# Connectors.net
KiCad netlist of a schematic drawn in Altium Designer
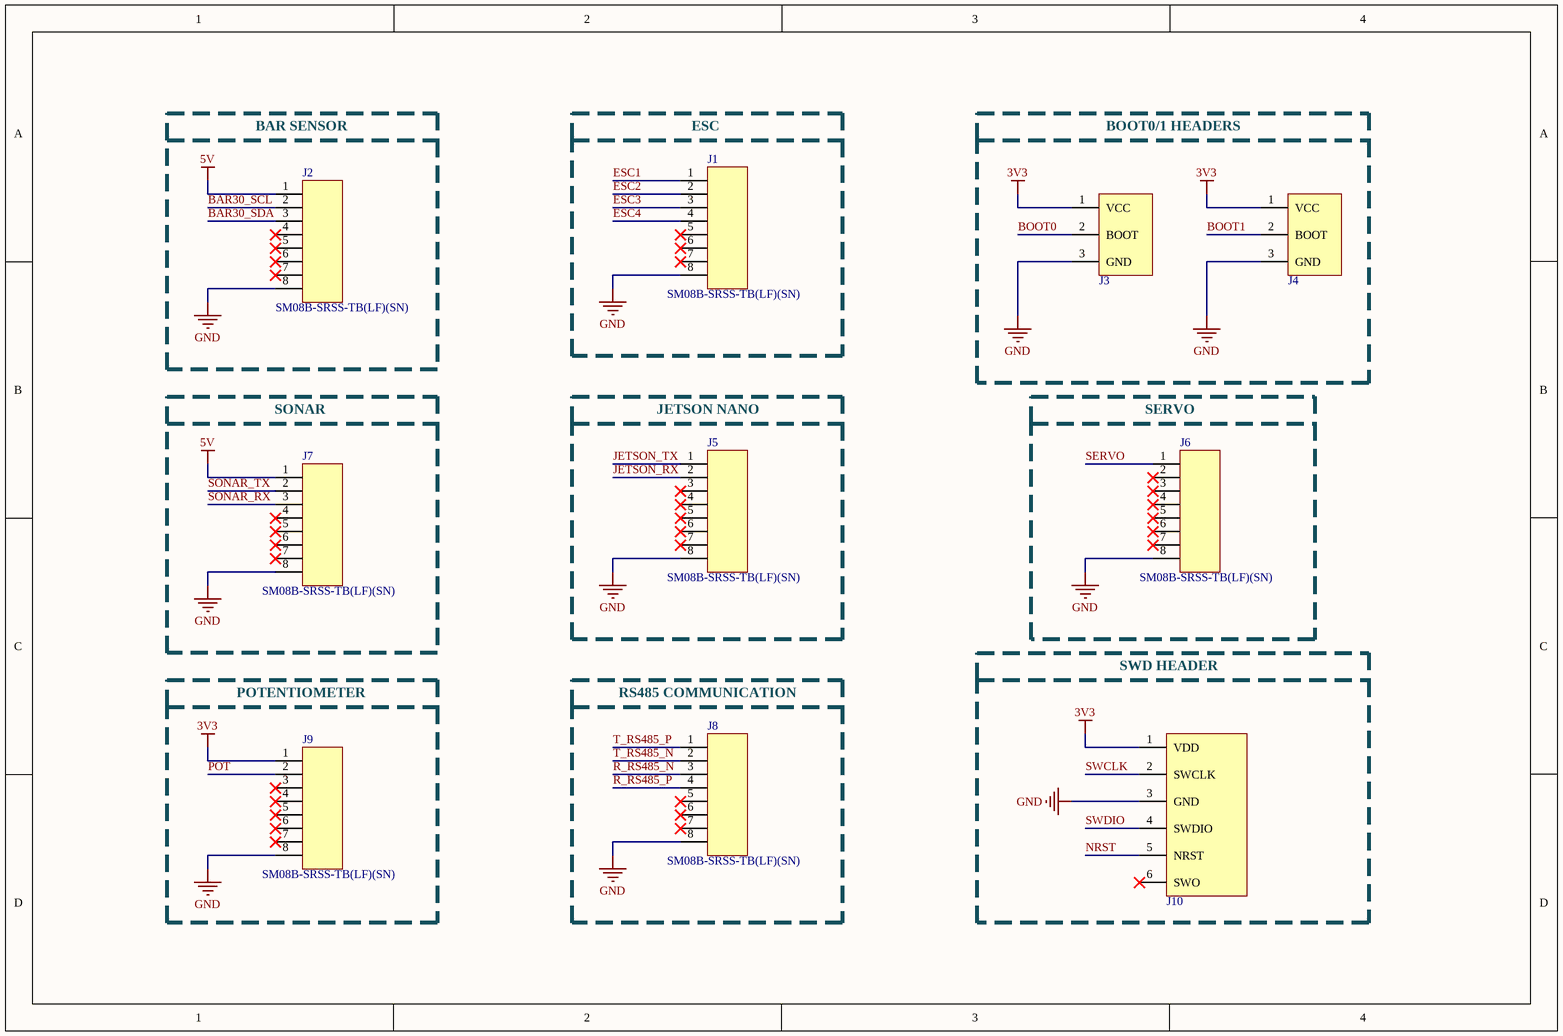
[diagram p0: Connectors.SchDoc]

(export (version "E")
  (design (tool "Eeschema 10.0.6"))
  (components
    (comp (ref "J1")
      (value "SM08B-SRSS-TB(LF)(SN)")
      (footprint "8 PIN HEADER")
      (description "Connector Header, Side Entry, SR Series, 8 Position, 1.00mm, 50V, Surface Mount, Tin, Natural")
      (fields (field (name "MANUFACTURER") "JST") (field (name "DESIGNED BY") "ADAK"))
      (libsource (lib "Integrated_Library5") (part "SM08B-SRSS-TB(LF)(SN)"))
    )
    (comp (ref "J2")
      (value "SM08B-SRSS-TB(LF)(SN)")
      (footprint "8 PIN HEADER")
      (description "Connector Header, Side Entry, SR Series, 8 Position, 1.00mm, 50V, Surface Mount, Tin, Natural")
      (fields (field (name "MANUFACTURER") "JST") (field (name "DESIGNED BY") "ADAK"))
      (libsource (lib "Integrated_Library5") (part "SM08B-SRSS-TB(LF)(SN)"))
    )
    (comp (ref "J3")
      (value "61300311121")
      (footprint "BOOT HEADER")
      (description "CONN HEADER VERT 3POS 2.54MM")
      (fields (field (name "MANUFACTURER") "Wurth Electronics") (field (name "DESIGNED BY") "ADAK"))
      (libsource (lib "Integrated_Library5") (part "61300311121"))
    )
    (comp (ref "J4")
      (value "61300311121")
      (footprint "BOOT HEADER")
      (description "CONN HEADER VERT 3POS 2.54MM")
      (fields (field (name "MANUFACTURER") "Wurth Electronics") (field (name "DESIGNED BY") "ADAK"))
      (libsource (lib "Integrated_Library5") (part "61300311121"))
    )
    (comp (ref "J5")
      (value "SM08B-SRSS-TB(LF)(SN)")
      (footprint "8 PIN HEADER")
      (description "Connector Header, Side Entry, SR Series, 8 Position, 1.00mm, 50V, Surface Mount, Tin, Natural")
      (fields (field (name "MANUFACTURER") "JST") (field (name "DESIGNED BY") "ADAK"))
      (libsource (lib "Integrated_Library5") (part "SM08B-SRSS-TB(LF)(SN)"))
    )
    (comp (ref "J6")
      (value "SM08B-SRSS-TB(LF)(SN)")
      (footprint "8 PIN HEADER")
      (description "Connector Header, Side Entry, SR Series, 8 Position, 1.00mm, 50V, Surface Mount, Tin, Natural")
      (fields (field (name "MANUFACTURER") "JST") (field (name "DESIGNED BY") "ADAK"))
      (libsource (lib "Integrated_Library5") (part "SM08B-SRSS-TB(LF)(SN)"))
    )
    (comp (ref "J7")
      (value "SM08B-SRSS-TB(LF)(SN)")
      (footprint "8 PIN HEADER")
      (description "Connector Header, Side Entry, SR Series, 8 Position, 1.00mm, 50V, Surface Mount, Tin, Natural")
      (fields (field (name "MANUFACTURER") "JST") (field (name "DESIGNED BY") "ADAK"))
      (libsource (lib "Integrated_Library5") (part "SM08B-SRSS-TB(LF)(SN)"))
    )
    (comp (ref "J8")
      (value "SM08B-SRSS-TB(LF)(SN)")
      (footprint "8 PIN HEADER")
      (description "Connector Header, Side Entry, SR Series, 8 Position, 1.00mm, 50V, Surface Mount, Tin, Natural")
      (fields (field (name "MANUFACTURER") "JST") (field (name "DESIGNED BY") "ADAK"))
      (libsource (lib "Integrated_Library5") (part "SM08B-SRSS-TB(LF)(SN)"))
    )
    (comp (ref "J9")
      (value "SM08B-SRSS-TB(LF)(SN)")
      (footprint "8 PIN HEADER")
      (description "Connector Header, Side Entry, SR Series, 8 Position, 1.00mm, 50V, Surface Mount, Tin, Natural")
      (fields (field (name "MANUFACTURER") "JST") (field (name "DESIGNED BY") "ADAK"))
      (libsource (lib "Integrated_Library5") (part "SM08B-SRSS-TB(LF)(SN)"))
    )
    (comp (ref "J10")
      (value "61300611121")
      (footprint "SWD HEADER")
      (description "CONN HEADER VERT 6POS 2.54MM")
      (fields (field (name "MANUFACTURER") "Wurth Electronics") (field (name "DESIGNED BY") "ADAK"))
      (libsource (lib "Integrated_Library5") (part "61300611121"))
    )
  )
  (nets
    (net (code "1") (name "/BAR30_SCL") (class "Default")
      (node (ref "J2") (pin "2") (pinfunction "2_2") (pintype "passive"))
    )
    (net (code "2") (name "/BAR30_SDA") (class "Default")
      (node (ref "J2") (pin "3") (pinfunction "3_3") (pintype "passive"))
    )
    (net (code "3") (name "/BOOT0") (class "Default")
      (node (ref "J3") (pin "2") (pinfunction "BOOT_2") (pintype "passive"))
    )
    (net (code "4") (name "/BOOT1") (class "Default")
      (node (ref "J4") (pin "2") (pinfunction "BOOT_2") (pintype "passive"))
    )
    (net (code "5") (name "/ESC1") (class "Default")
      (node (ref "J1") (pin "1") (pinfunction "1_1") (pintype "passive"))
    )
    (net (code "6") (name "/ESC2") (class "Default")
      (node (ref "J1") (pin "2") (pinfunction "2_2") (pintype "passive"))
    )
    (net (code "7") (name "/ESC3") (class "Default")
      (node (ref "J1") (pin "3") (pinfunction "3_3") (pintype "passive"))
    )
    (net (code "8") (name "/ESC4") (class "Default")
      (node (ref "J1") (pin "4") (pinfunction "4_4") (pintype "passive"))
    )
    (net (code "9") (name "/JETSON_RX") (class "Default")
      (node (ref "J5") (pin "2") (pinfunction "2_2") (pintype "passive"))
    )
    (net (code "10") (name "/JETSON_TX") (class "Default")
      (node (ref "J5") (pin "1") (pinfunction "1_1") (pintype "passive"))
    )
    (net (code "11") (name "/NRST") (class "Default")
      (node (ref "J10") (pin "5") (pinfunction "NRST_5") (pintype "passive"))
    )
    (net (code "12") (name "/POT") (class "Default")
      (node (ref "J9") (pin "2") (pinfunction "2_2") (pintype "passive"))
    )
    (net (code "13") (name "/R_RS485_N") (class "Default")
      (node (ref "J8") (pin "3") (pinfunction "3_3") (pintype "passive"))
    )
    (net (code "14") (name "/R_RS485_P") (class "Default")
      (node (ref "J8") (pin "4") (pinfunction "4_4") (pintype "passive"))
    )
    (net (code "15") (name "/SERVO") (class "Default")
      (node (ref "J6") (pin "1") (pinfunction "1_1") (pintype "passive"))
    )
    (net (code "16") (name "/SONAR_RX") (class "Default")
      (node (ref "J7") (pin "3") (pinfunction "3_3") (pintype "passive"))
    )
    (net (code "17") (name "/SONAR_TX") (class "Default")
      (node (ref "J7") (pin "2") (pinfunction "2_2") (pintype "passive"))
    )
    (net (code "18") (name "/SWCLK") (class "Default")
      (node (ref "J10") (pin "2") (pinfunction "SWCLK_2") (pintype "passive"))
    )
    (net (code "19") (name "/SWDIO") (class "Default")
      (node (ref "J10") (pin "4") (pinfunction "SWDIO_4") (pintype "passive"))
    )
    (net (code "20") (name "/T_RS485_N") (class "Default")
      (node (ref "J8") (pin "2") (pinfunction "2_2") (pintype "passive"))
    )
    (net (code "21") (name "/T_RS485_P") (class "Default")
      (node (ref "J8") (pin "1") (pinfunction "1_1") (pintype "passive"))
    )
    (net (code "22") (name "3V3") (class "Default")
      (node (ref "J10") (pin "1") (pinfunction "VDD_1") (pintype "passive"))
      (node (ref "J3") (pin "1") (pinfunction "VCC_1") (pintype "passive"))
      (node (ref "J4") (pin "1") (pinfunction "VCC_1") (pintype "passive"))
      (node (ref "J9") (pin "1") (pinfunction "1_1") (pintype "passive"))
    )
    (net (code "23") (name "5V") (class "Default")
      (node (ref "J2") (pin "1") (pinfunction "1_1") (pintype "passive"))
      (node (ref "J7") (pin "1") (pinfunction "1_1") (pintype "passive"))
    )
    (net (code "24") (name "GND") (class "Default")
      (node (ref "J1") (pin "8") (pinfunction "8_8") (pintype "passive"))
      (node (ref "J10") (pin "3") (pinfunction "GND_3") (pintype "passive"))
      (node (ref "J2") (pin "8") (pinfunction "8_8") (pintype "passive"))
      (node (ref "J3") (pin "3") (pinfunction "GND_3") (pintype "passive"))
      (node (ref "J4") (pin "3") (pinfunction "GND_3") (pintype "passive"))
      (node (ref "J5") (pin "8") (pinfunction "8_8") (pintype "passive"))
      (node (ref "J6") (pin "8") (pinfunction "8_8") (pintype "passive"))
      (node (ref "J7") (pin "8") (pinfunction "8_8") (pintype "passive"))
      (node (ref "J8") (pin "8") (pinfunction "8_8") (pintype "passive"))
      (node (ref "J9") (pin "8") (pinfunction "8_8") (pintype "passive"))
    )
    (net (code "25") (name "unconnected-(J1-Pad5)") (class "Default")
      (node (ref "J1") (pin "5") (pinfunction "5_5") (pintype "passive+no_connect"))
    )
    (net (code "26") (name "unconnected-(J1-Pad6)") (class "Default")
      (node (ref "J1") (pin "6") (pinfunction "6_6") (pintype "passive+no_connect"))
    )
    (net (code "27") (name "unconnected-(J1-Pad7)") (class "Default")
      (node (ref "J1") (pin "7") (pinfunction "7_7") (pintype "passive+no_connect"))
    )
    (net (code "28") (name "unconnected-(J2-Pad4)") (class "Default")
      (node (ref "J2") (pin "4") (pinfunction "4_4") (pintype "passive+no_connect"))
    )
    (net (code "29") (name "unconnected-(J2-Pad5)") (class "Default")
      (node (ref "J2") (pin "5") (pinfunction "5_5") (pintype "passive+no_connect"))
    )
    (net (code "30") (name "unconnected-(J2-Pad6)") (class "Default")
      (node (ref "J2") (pin "6") (pinfunction "6_6") (pintype "passive+no_connect"))
    )
    (net (code "31") (name "unconnected-(J2-Pad7)") (class "Default")
      (node (ref "J2") (pin "7") (pinfunction "7_7") (pintype "passive+no_connect"))
    )
    (net (code "32") (name "unconnected-(J5-Pad3)") (class "Default")
      (node (ref "J5") (pin "3") (pinfunction "3_3") (pintype "passive+no_connect"))
    )
    (net (code "33") (name "unconnected-(J5-Pad4)") (class "Default")
      (node (ref "J5") (pin "4") (pinfunction "4_4") (pintype "passive+no_connect"))
    )
    (net (code "34") (name "unconnected-(J5-Pad5)") (class "Default")
      (node (ref "J5") (pin "5") (pinfunction "5_5") (pintype "passive+no_connect"))
    )
    (net (code "35") (name "unconnected-(J5-Pad6)") (class "Default")
      (node (ref "J5") (pin "6") (pinfunction "6_6") (pintype "passive+no_connect"))
    )
    (net (code "36") (name "unconnected-(J5-Pad7)") (class "Default")
      (node (ref "J5") (pin "7") (pinfunction "7_7") (pintype "passive+no_connect"))
    )
    (net (code "37") (name "unconnected-(J6-Pad2)") (class "Default")
      (node (ref "J6") (pin "2") (pinfunction "2_2") (pintype "passive+no_connect"))
    )
    (net (code "38") (name "unconnected-(J6-Pad3)") (class "Default")
      (node (ref "J6") (pin "3") (pinfunction "3_3") (pintype "passive+no_connect"))
    )
    (net (code "39") (name "unconnected-(J6-Pad4)") (class "Default")
      (node (ref "J6") (pin "4") (pinfunction "4_4") (pintype "passive+no_connect"))
    )
    (net (code "40") (name "unconnected-(J6-Pad5)") (class "Default")
      (node (ref "J6") (pin "5") (pinfunction "5_5") (pintype "passive+no_connect"))
    )
    (net (code "41") (name "unconnected-(J6-Pad6)") (class "Default")
      (node (ref "J6") (pin "6") (pinfunction "6_6") (pintype "passive+no_connect"))
    )
    (net (code "42") (name "unconnected-(J6-Pad7)") (class "Default")
      (node (ref "J6") (pin "7") (pinfunction "7_7") (pintype "passive+no_connect"))
    )
    (net (code "43") (name "unconnected-(J7-Pad4)") (class "Default")
      (node (ref "J7") (pin "4") (pinfunction "4_4") (pintype "passive+no_connect"))
    )
    (net (code "44") (name "unconnected-(J7-Pad5)") (class "Default")
      (node (ref "J7") (pin "5") (pinfunction "5_5") (pintype "passive+no_connect"))
    )
    (net (code "45") (name "unconnected-(J7-Pad6)") (class "Default")
      (node (ref "J7") (pin "6") (pinfunction "6_6") (pintype "passive+no_connect"))
    )
    (net (code "46") (name "unconnected-(J7-Pad7)") (class "Default")
      (node (ref "J7") (pin "7") (pinfunction "7_7") (pintype "passive+no_connect"))
    )
    (net (code "47") (name "unconnected-(J8-Pad5)") (class "Default")
      (node (ref "J8") (pin "5") (pinfunction "5_5") (pintype "passive+no_connect"))
    )
    (net (code "48") (name "unconnected-(J8-Pad6)") (class "Default")
      (node (ref "J8") (pin "6") (pinfunction "6_6") (pintype "passive+no_connect"))
    )
    (net (code "49") (name "unconnected-(J8-Pad7)") (class "Default")
      (node (ref "J8") (pin "7") (pinfunction "7_7") (pintype "passive+no_connect"))
    )
    (net (code "50") (name "unconnected-(J9-Pad3)") (class "Default")
      (node (ref "J9") (pin "3") (pinfunction "3_3") (pintype "passive+no_connect"))
    )
    (net (code "51") (name "unconnected-(J9-Pad4)") (class "Default")
      (node (ref "J9") (pin "4") (pinfunction "4_4") (pintype "passive+no_connect"))
    )
    (net (code "52") (name "unconnected-(J9-Pad5)") (class "Default")
      (node (ref "J9") (pin "5") (pinfunction "5_5") (pintype "passive+no_connect"))
    )
    (net (code "53") (name "unconnected-(J9-Pad6)") (class "Default")
      (node (ref "J9") (pin "6") (pinfunction "6_6") (pintype "passive+no_connect"))
    )
    (net (code "54") (name "unconnected-(J9-Pad7)") (class "Default")
      (node (ref "J9") (pin "7") (pinfunction "7_7") (pintype "passive+no_connect"))
    )
    (net (code "55") (name "unconnected-(J10-SWO-Pad6)") (class "Default")
      (node (ref "J10") (pin "6") (pinfunction "SWO_6") (pintype "passive+no_connect"))
    )
  )
)
